# Mono_Slider2.net
KiCad netlist of a schematic drawn in EAGLE
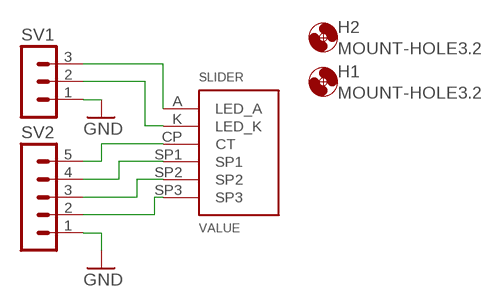
[diagram p0: schematic, sheet 1]

(export (version "E")
  (design (tool "Eeschema 10.0.6"))
  (components
    (comp (ref "H1")
      (value "MOUNT-HOLE3.2")
      (footprint "eagle-import:3,2")
      (libsource (lib "eagle-import") (part "MOUNT-HOLE3.2"))
    )
    (comp (ref "H2")
      (value "MOUNT-HOLE3.2")
      (footprint "eagle-import:3,2")
      (libsource (lib "eagle-import") (part "MOUNT-HOLE3.2"))
    )
    (comp (ref "SL1")
      (value "SLIDER")
      (footprint "eagle-import:SLIDER_SMALL")
      (libsource (lib "eagle-import") (part "SLIDERSLIDER_SMALL"))
    )
    (comp (ref "SV1")
      (value "MA03-1")
      (footprint "eagle-import:MA03-1")
      (libsource (lib "eagle-import") (part "MA03-1"))
    )
    (comp (ref "SV2")
      (value "MA05-1")
      (footprint "eagle-import:MA05-1")
      (libsource (lib "eagle-import") (part "MA05-1"))
    )
  )
  (nets
    (net (code "1") (name "GND") (class "Default")
      (node (ref "SV1") (pin "1") (pinfunction "1_1") (pintype "passive"))
      (node (ref "SV2") (pin "1") (pinfunction "1_1") (pintype "passive"))
    )
    (net (code "2") (name "Net-(SL1-CT)") (class "Default")
      (node (ref "SL1") (pin "CP") (pinfunction "CT_CP") (pintype "bidirectional"))
      (node (ref "SV2") (pin "5") (pinfunction "5_5") (pintype "passive"))
    )
    (net (code "3") (name "Net-(SL1-LED_A)") (class "Default")
      (node (ref "SL1") (pin "A") (pinfunction "LED_A_A") (pintype "power_in"))
      (node (ref "SV1") (pin "3") (pinfunction "3_3") (pintype "passive"))
    )
    (net (code "4") (name "Net-(SL1-LED_K)") (class "Default")
      (node (ref "SL1") (pin "K") (pinfunction "LED_K_K") (pintype "power_in"))
      (node (ref "SV1") (pin "2") (pinfunction "2_2") (pintype "passive"))
    )
    (net (code "5") (name "Net-(SL1-PadSP1)") (class "Default")
      (node (ref "SL1") (pin "SP1") (pinfunction "SP1_SP1") (pintype "bidirectional"))
      (node (ref "SV2") (pin "4") (pinfunction "4_4") (pintype "passive"))
    )
    (net (code "6") (name "Net-(SL1-PadSP2)") (class "Default")
      (node (ref "SL1") (pin "SP2") (pinfunction "SP2_SP2") (pintype "bidirectional"))
      (node (ref "SV2") (pin "3") (pinfunction "3_3") (pintype "passive"))
    )
    (net (code "7") (name "Net-(SL1-PadSP3)") (class "Default")
      (node (ref "SL1") (pin "SP3") (pinfunction "SP3_SP3") (pintype "bidirectional"))
      (node (ref "SV2") (pin "2") (pinfunction "2_2") (pintype "passive"))
    )
  )
)
